# Power.net
KiCad netlist of a schematic drawn in Altium Designer
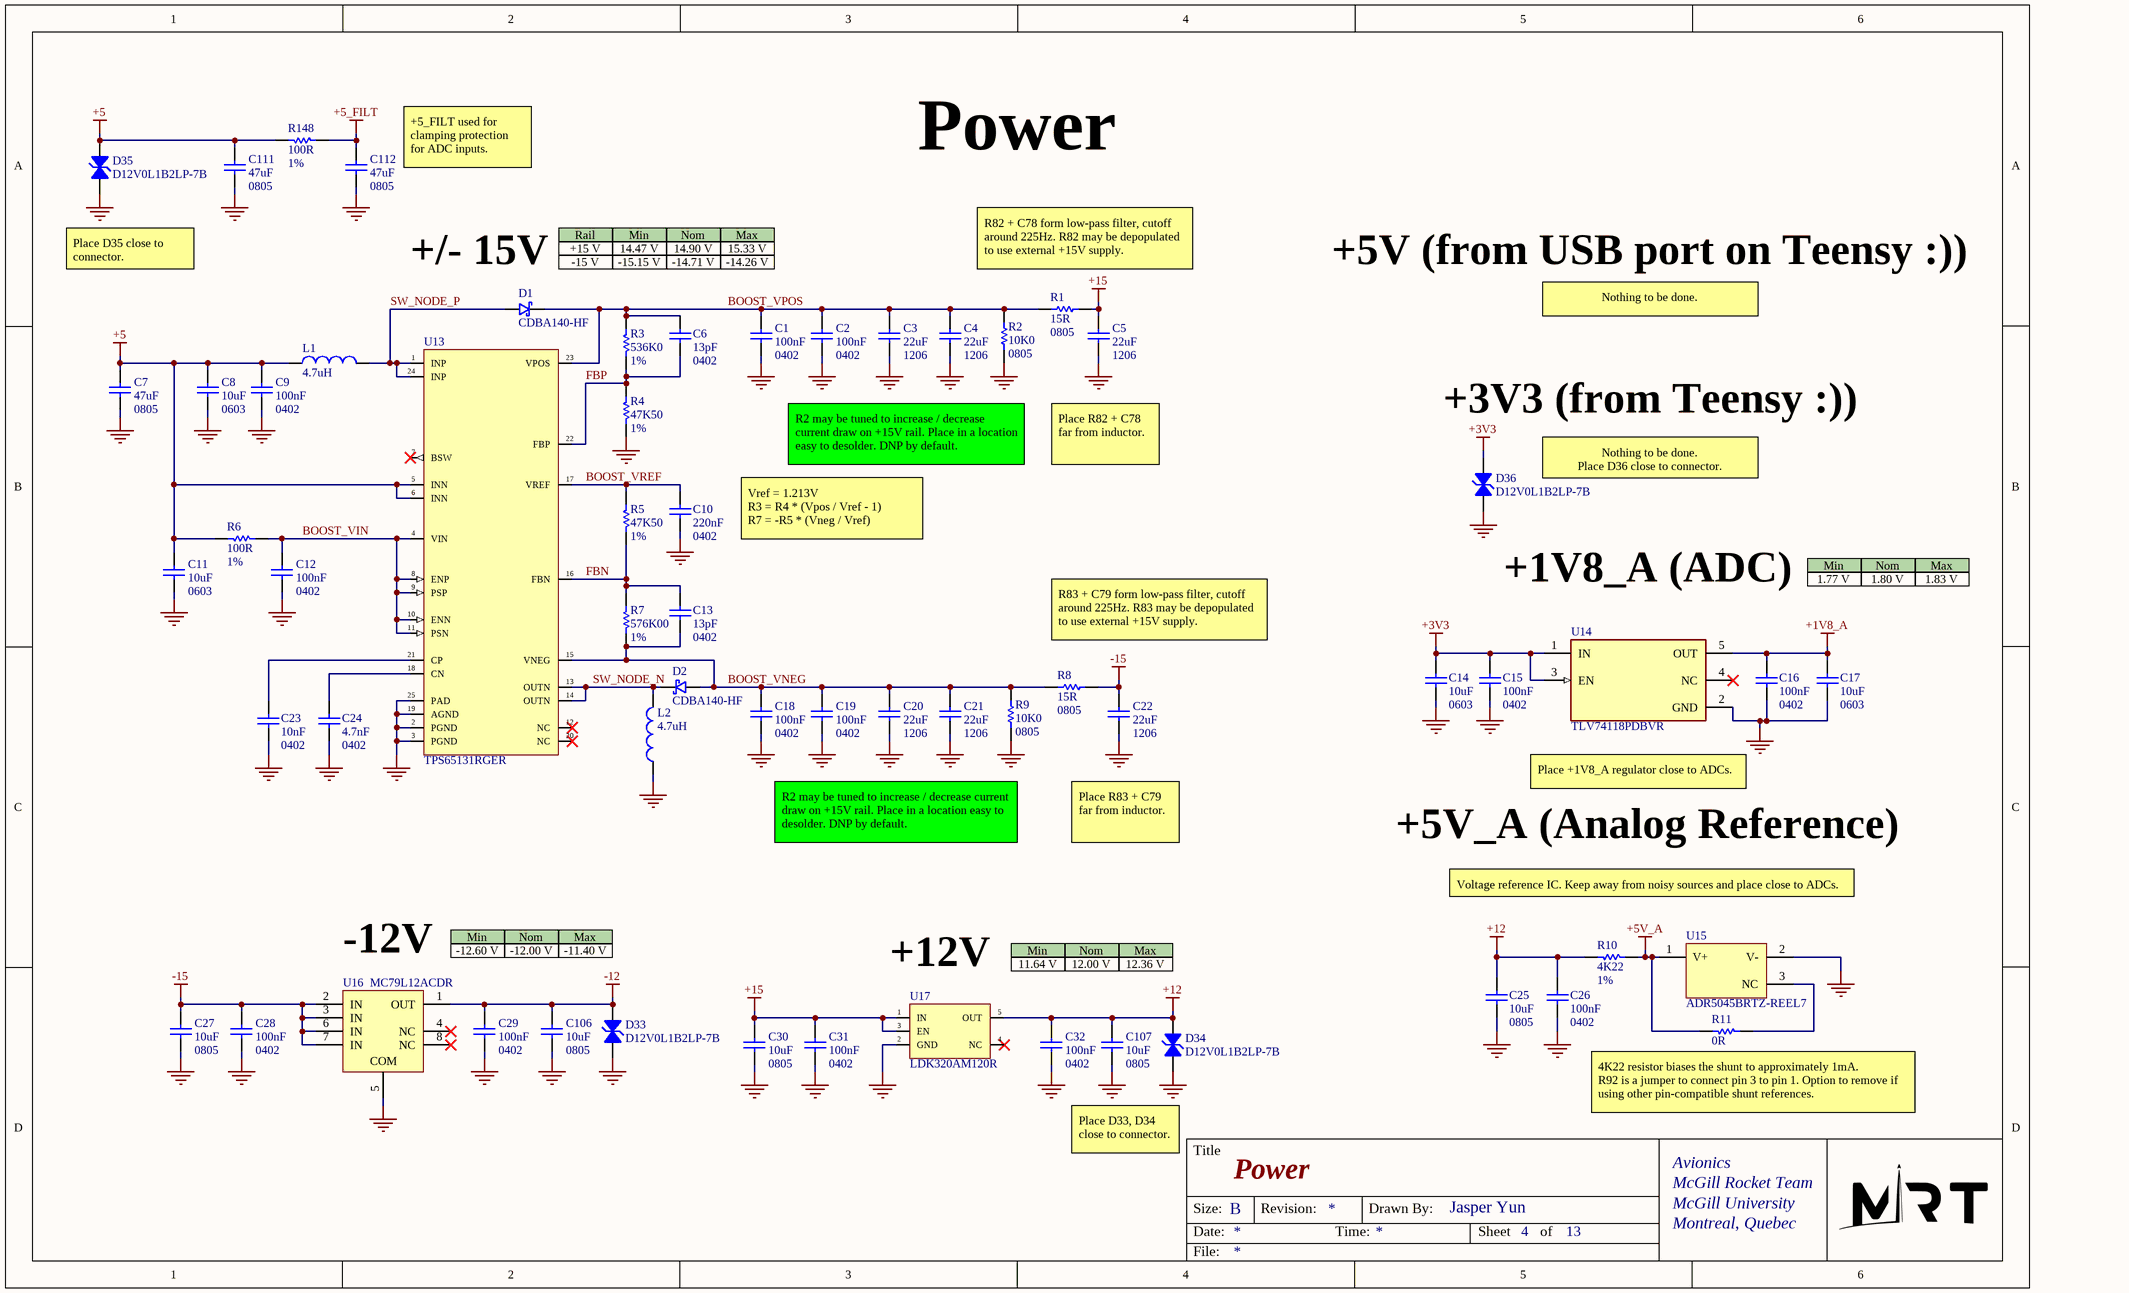
[diagram p0: Power.SchDoc]

(export (version "E")
  (design (tool "Eeschema 10.0.6"))
  (components
    (comp (ref "C1")
      (value "100nF")
      (footprint "0402 CAP")
      (description "Capacitor")
      (fields (field (name "ALTIUM_VALUE") "0402") (field (name "PUBLISHER") "Altium Limited"))
      (libsource (lib "Miscellaneous Devices") (part "Cap"))
    )
    (comp (ref "C2")
      (value "100nF")
      (footprint "0402 CAP")
      (description "Capacitor")
      (fields (field (name "ALTIUM_VALUE") "0402") (field (name "PUBLISHER") "Altium Limited"))
      (libsource (lib "Miscellaneous Devices") (part "Cap"))
    )
    (comp (ref "C3")
      (value "22uF")
      (footprint "1206 CAP")
      (description "Capacitor")
      (fields (field (name "ALTIUM_VALUE") "1206") (field (name "PUBLISHER") "Altium Limited"))
      (libsource (lib "Miscellaneous Devices") (part "Cap"))
    )
    (comp (ref "C4")
      (value "22uF")
      (footprint "1206 CAP")
      (description "Capacitor")
      (fields (field (name "ALTIUM_VALUE") "1206") (field (name "PUBLISHER") "Altium Limited"))
      (libsource (lib "Miscellaneous Devices") (part "Cap"))
    )
    (comp (ref "C5")
      (value "22uF")
      (footprint "1206 CAP")
      (description "Capacitor")
      (fields (field (name "ALTIUM_VALUE") "1206") (field (name "PUBLISHER") "Altium Limited"))
      (libsource (lib "Miscellaneous Devices") (part "Cap"))
    )
    (comp (ref "C6")
      (value "13pF")
      (footprint "0402 CAP")
      (description "Capacitor")
      (fields (field (name "ALTIUM_VALUE") "0402") (field (name "PUBLISHER") "Altium Limited"))
      (libsource (lib "Miscellaneous Devices") (part "Cap"))
    )
    (comp (ref "C7")
      (value "47uF")
      (footprint "0805 CAP")
      (description "Capacitor")
      (fields (field (name "ALTIUM_VALUE") "0805") (field (name "PUBLISHER") "Altium Limited"))
      (libsource (lib "Miscellaneous Devices") (part "Cap"))
    )
    (comp (ref "C8")
      (value "10uF")
      (footprint "0603 CAP SAMSUNG CL10C")
      (description "Capacitor")
      (fields (field (name "ALTIUM_VALUE") "0603") (field (name "PUBLISHER") "Altium Limited"))
      (libsource (lib "Miscellaneous Devices") (part "Cap"))
    )
    (comp (ref "C9")
      (value "100nF")
      (footprint "0402 CAP")
      (description "Capacitor")
      (fields (field (name "ALTIUM_VALUE") "0402") (field (name "PUBLISHER") "Altium Limited"))
      (libsource (lib "Miscellaneous Devices") (part "Cap"))
    )
    (comp (ref "C10")
      (value "220nF")
      (footprint "0402 CAP")
      (description "Capacitor")
      (fields (field (name "ALTIUM_VALUE") "0402") (field (name "PUBLISHER") "Altium Limited"))
      (libsource (lib "Miscellaneous Devices") (part "Cap"))
    )
    (comp (ref "C11")
      (value "10uF")
      (footprint "0603 CAP SAMSUNG CL10C")
      (description "Capacitor")
      (fields (field (name "ALTIUM_VALUE") "0603") (field (name "PUBLISHER") "Altium Limited"))
      (libsource (lib "Miscellaneous Devices") (part "Cap"))
    )
    (comp (ref "C12")
      (value "100nF")
      (footprint "0402 CAP")
      (description "Capacitor")
      (fields (field (name "ALTIUM_VALUE") "0402") (field (name "PUBLISHER") "Altium Limited"))
      (libsource (lib "Miscellaneous Devices") (part "Cap"))
    )
    (comp (ref "C13")
      (value "13pF")
      (footprint "0402 CAP")
      (description "Capacitor")
      (fields (field (name "ALTIUM_VALUE") "0402") (field (name "PUBLISHER") "Altium Limited"))
      (libsource (lib "Miscellaneous Devices") (part "Cap"))
    )
    (comp (ref "C14")
      (value "10uF")
      (footprint "0603 CAP SAMSUNG CL10C")
      (description "Capacitor")
      (fields (field (name "ALTIUM_VALUE") "0603") (field (name "PUBLISHER") "Altium Limited"))
      (libsource (lib "Miscellaneous Devices") (part "Cap"))
    )
    (comp (ref "C15")
      (value "100nF")
      (footprint "0402 CAP")
      (description "Capacitor")
      (fields (field (name "ALTIUM_VALUE") "0402") (field (name "PUBLISHER") "Altium Limited"))
      (libsource (lib "Miscellaneous Devices") (part "Cap"))
    )
    (comp (ref "C16")
      (value "100nF")
      (footprint "0402 CAP")
      (description "Capacitor")
      (fields (field (name "ALTIUM_VALUE") "0402") (field (name "PUBLISHER") "Altium Limited"))
      (libsource (lib "Miscellaneous Devices") (part "Cap"))
    )
    (comp (ref "C17")
      (value "10uF")
      (footprint "0603 CAP SAMSUNG CL10C")
      (description "Capacitor")
      (fields (field (name "ALTIUM_VALUE") "0603") (field (name "PUBLISHER") "Altium Limited"))
      (libsource (lib "Miscellaneous Devices") (part "Cap"))
    )
    (comp (ref "C18")
      (value "100nF")
      (footprint "0402 CAP")
      (description "Capacitor")
      (fields (field (name "ALTIUM_VALUE") "0402") (field (name "PUBLISHER") "Altium Limited"))
      (libsource (lib "Miscellaneous Devices") (part "Cap"))
    )
    (comp (ref "C19")
      (value "100nF")
      (footprint "0402 CAP")
      (description "Capacitor")
      (fields (field (name "ALTIUM_VALUE") "0402") (field (name "PUBLISHER") "Altium Limited"))
      (libsource (lib "Miscellaneous Devices") (part "Cap"))
    )
    (comp (ref "C20")
      (value "22uF")
      (footprint "1206 CAP")
      (description "Capacitor")
      (fields (field (name "ALTIUM_VALUE") "1206") (field (name "PUBLISHER") "Altium Limited"))
      (libsource (lib "Miscellaneous Devices") (part "Cap"))
    )
    (comp (ref "C21")
      (value "22uF")
      (footprint "1206 CAP")
      (description "Capacitor")
      (fields (field (name "ALTIUM_VALUE") "1206") (field (name "PUBLISHER") "Altium Limited"))
      (libsource (lib "Miscellaneous Devices") (part "Cap"))
    )
    (comp (ref "C22")
      (value "22uF")
      (footprint "1206 CAP")
      (description "Capacitor")
      (fields (field (name "ALTIUM_VALUE") "1206") (field (name "PUBLISHER") "Altium Limited"))
      (libsource (lib "Miscellaneous Devices") (part "Cap"))
    )
    (comp (ref "C23")
      (value "10nF")
      (footprint "0402 CAP")
      (description "Capacitor")
      (fields (field (name "ALTIUM_VALUE") "0402") (field (name "PUBLISHER") "Altium Limited"))
      (libsource (lib "Miscellaneous Devices") (part "Cap"))
    )
    (comp (ref "C24")
      (value "4.7nF")
      (footprint "0402 CAP")
      (description "Capacitor")
      (fields (field (name "ALTIUM_VALUE") "0402") (field (name "PUBLISHER") "Altium Limited"))
      (libsource (lib "Miscellaneous Devices") (part "Cap"))
    )
    (comp (ref "C25")
      (value "10uF")
      (footprint "0805 CAP")
      (description "Capacitor")
      (fields (field (name "ALTIUM_VALUE") "0805") (field (name "PUBLISHER") "Altium Limited"))
      (libsource (lib "Miscellaneous Devices") (part "Cap"))
    )
    (comp (ref "C26")
      (value "100nF")
      (footprint "0402 CAP")
      (description "Capacitor")
      (fields (field (name "ALTIUM_VALUE") "0402") (field (name "PUBLISHER") "Altium Limited"))
      (libsource (lib "Miscellaneous Devices") (part "Cap"))
    )
    (comp (ref "C27")
      (value "10uF")
      (footprint "0805 CAP")
      (description "Capacitor")
      (fields (field (name "ALTIUM_VALUE") "0805") (field (name "PUBLISHER") "Altium Limited"))
      (libsource (lib "Miscellaneous Devices") (part "Cap"))
    )
    (comp (ref "C28")
      (value "100nF")
      (footprint "0402 CAP")
      (description "Capacitor")
      (fields (field (name "ALTIUM_VALUE") "0402") (field (name "PUBLISHER") "Altium Limited"))
      (libsource (lib "Miscellaneous Devices") (part "Cap"))
    )
    (comp (ref "C29")
      (value "100nF")
      (footprint "0402 CAP")
      (description "Capacitor")
      (fields (field (name "ALTIUM_VALUE") "0402") (field (name "PUBLISHER") "Altium Limited"))
      (libsource (lib "Miscellaneous Devices") (part "Cap"))
    )
    (comp (ref "C30")
      (value "10uF")
      (footprint "0805 CAP")
      (description "Capacitor")
      (fields (field (name "ALTIUM_VALUE") "0805") (field (name "PUBLISHER") "Altium Limited"))
      (libsource (lib "Miscellaneous Devices") (part "Cap"))
    )
    (comp (ref "C31")
      (value "100nF")
      (footprint "0402 CAP")
      (description "Capacitor")
      (fields (field (name "ALTIUM_VALUE") "0402") (field (name "PUBLISHER") "Altium Limited"))
      (libsource (lib "Miscellaneous Devices") (part "Cap"))
    )
    (comp (ref "C32")
      (value "100nF")
      (footprint "0402 CAP")
      (description "Capacitor")
      (fields (field (name "ALTIUM_VALUE") "0402") (field (name "PUBLISHER") "Altium Limited"))
      (libsource (lib "Miscellaneous Devices") (part "Cap"))
    )
    (comp (ref "C106")
      (value "10uF")
      (footprint "0805 CAP")
      (description "Capacitor")
      (fields (field (name "ALTIUM_VALUE") "0805") (field (name "PUBLISHER") "Altium Limited"))
      (libsource (lib "Miscellaneous Devices") (part "Cap"))
    )
    (comp (ref "C107")
      (value "10uF")
      (footprint "0805 CAP")
      (description "Capacitor")
      (fields (field (name "ALTIUM_VALUE") "0805") (field (name "PUBLISHER") "Altium Limited"))
      (libsource (lib "Miscellaneous Devices") (part "Cap"))
    )
    (comp (ref "C111")
      (value "47uF")
      (footprint "0805 CAP")
      (description "Capacitor")
      (fields (field (name "ALTIUM_VALUE") "0805") (field (name "PUBLISHER") "Altium Limited"))
      (libsource (lib "Miscellaneous Devices") (part "Cap"))
    )
    (comp (ref "C112")
      (value "47uF")
      (footprint "0805 CAP")
      (description "Capacitor")
      (fields (field (name "ALTIUM_VALUE") "0805") (field (name "PUBLISHER") "Altium Limited"))
      (libsource (lib "Miscellaneous Devices") (part "Cap"))
    )
    (comp (ref "D1")
      (value "CDBA140-HF")
      (footprint "Diode SMA")
      (description "Generic Schottky Diode")
      (libsource (lib "MRT SCH Library") (part "Schottky Diode"))
    )
    (comp (ref "D2")
      (value "CDBA140-HF")
      (footprint "Diode SMA")
      (description "Generic Schottky Diode")
      (libsource (lib "MRT SCH Library") (part "Schottky Diode"))
    )
    (comp (ref "D33")
      (value "D12V0L1B2LP-7B")
      (footprint "DFN1006-2")
      (description "Bidirectional Zener diode")
      (libsource (lib "MRT SCH Library") (part "Diode Zener Bidirectional"))
    )
    (comp (ref "D34")
      (value "D12V0L1B2LP-7B")
      (footprint "DFN1006-2")
      (description "Bidirectional Zener diode")
      (libsource (lib "MRT SCH Library") (part "Diode Zener Bidirectional"))
    )
    (comp (ref "D35")
      (value "D12V0L1B2LP-7B")
      (footprint "DFN1006-2")
      (description "Bidirectional Zener diode")
      (libsource (lib "MRT SCH Library") (part "Diode Zener Bidirectional"))
    )
    (comp (ref "D36")
      (value "D12V0L1B2LP-7B")
      (footprint "DFN1006-2")
      (description "Bidirectional Zener diode")
      (libsource (lib "MRT SCH Library") (part "Diode Zener Bidirectional"))
    )
    (comp (ref "L1")
      (value "4.7uH")
      (footprint "Inductor BWVS005050403R3M00")
      (description "4.7uH  BWVS005050404R7M00")
      (fields (field (name "PUBLISHER") "Altium Limited"))
      (libsource (lib "Miscellaneous Devices") (part "Inductor"))
    )
    (comp (ref "L2")
      (value "4.7uH")
      (footprint "Inductor BWVS005050403R3M00")
      (description "4.7uH  BWVS005050404R7M00")
      (fields (field (name "PUBLISHER") "Altium Limited"))
      (libsource (lib "Miscellaneous Devices") (part "Inductor"))
    )
    (comp (ref "R1")
      (value "15R")
      (footprint "0805 RES")
      (description "Resistor")
      (fields (field (name "ALTIUM_VALUE") "0805") (field (name "PUBLISHER") "Altium Limited"))
      (libsource (lib "Miscellaneous Devices") (part "Res1"))
    )
    (comp (ref "R2")
      (value "10K0")
      (footprint "0805 RES")
      (description "Resistor")
      (fields (field (name "ALTIUM_VALUE") "0805") (field (name "PUBLISHER") "Altium Limited"))
      (libsource (lib "Miscellaneous Devices") (part "Res1"))
    )
    (comp (ref "R3")
      (value "536K0")
      (footprint "0402 RES")
      (description "Resistor")
      (fields (field (name "ALTIUM_VALUE") "1%") (field (name "PUBLISHER") "Altium Limited"))
      (libsource (lib "Miscellaneous Devices") (part "Res1"))
    )
    (comp (ref "R4")
      (value "47K50")
      (footprint "0402 RES")
      (description "Resistor")
      (fields (field (name "ALTIUM_VALUE") "1%") (field (name "PUBLISHER") "Altium Limited"))
      (libsource (lib "Miscellaneous Devices") (part "Res1"))
    )
    (comp (ref "R5")
      (value "47K50")
      (footprint "0402 RES")
      (description "Resistor")
      (fields (field (name "ALTIUM_VALUE") "1%") (field (name "PUBLISHER") "Altium Limited"))
      (libsource (lib "Miscellaneous Devices") (part "Res1"))
    )
    (comp (ref "R6")
      (value "100R")
      (footprint "0402 RES")
      (description "Resistor")
      (fields (field (name "ALTIUM_VALUE") "1%") (field (name "PUBLISHER") "Altium Limited"))
      (libsource (lib "Miscellaneous Devices") (part "Res1"))
    )
    (comp (ref "R7")
      (value "576K00")
      (footprint "0402 RES")
      (description "Resistor")
      (fields (field (name "ALTIUM_VALUE") "1%") (field (name "PUBLISHER") "Altium Limited"))
      (libsource (lib "Miscellaneous Devices") (part "Res1"))
    )
    (comp (ref "R8")
      (value "15R")
      (footprint "0805 RES")
      (description "Resistor")
      (fields (field (name "ALTIUM_VALUE") "0805") (field (name "PUBLISHER") "Altium Limited"))
      (libsource (lib "Miscellaneous Devices") (part "Res1"))
    )
    (comp (ref "R9")
      (value "10K0")
      (footprint "0805 RES")
      (description "Resistor")
      (fields (field (name "ALTIUM_VALUE") "0805") (field (name "PUBLISHER") "Altium Limited"))
      (libsource (lib "Miscellaneous Devices") (part "Res1"))
    )
    (comp (ref "R10")
      (value "4K22")
      (footprint "0402 RES")
      (description "Resistor")
      (fields (field (name "ALTIUM_VALUE") "1%") (field (name "PUBLISHER") "Altium Limited"))
      (libsource (lib "Miscellaneous Devices") (part "Res1"))
    )
    (comp (ref "R11")
      (value "0R")
      (footprint "0402 RES")
      (description "Resistor")
      (fields (field (name "PUBLISHER") "Altium Limited"))
      (libsource (lib "Miscellaneous Devices") (part "Res1"))
    )
    (comp (ref "R148")
      (value "100R")
      (footprint "0402 RES")
      (description "Resistor")
      (fields (field (name "ALTIUM_VALUE") "1%") (field (name "PUBLISHER") "Altium Limited"))
      (libsource (lib "Miscellaneous Devices") (part "Res1"))
    )
    (comp (ref "U13")
      (value "TPS65131RGER")
      (footprint "VQFN-24")
      (description "IC REG BUCK BST INV ADJ DL 24QFN")
      (fields (field (name "MANUFACTURER") "Texas Instruments"))
      (libsource (lib "MRT SCH Library") (part "Dual Boost TPS65131RGER"))
    )
    (comp (ref "U14")
      (value "TLV74118PDBVR")
      (footprint "FP-DBV0005A-IPC_A")
      (description "None")
      (libsource (lib "Altium Content Vault") (part "843f007849b3ee74adb27ff62509038"))
    )
    (comp (ref "U15")
      (value "ADR5045BRTZ-REEL7")
      (footprint "ADI-RT-3_M")
      (fields (field (name "MANUFACTURER") "Analog Devices"))
      (libsource (lib "Altium Content Vault") (part "ADI-ADR158x_504x-RT_KS-3"))
    )
    (comp (ref "U16")
      (value "MC79L12ACDR")
      (footprint "D0008A_M")
      (fields (field (name "MANUFACTURER") "Texas Instruments"))
      (libsource (lib "Altium Content Vault") (part "TI-MC79L12AD8"))
    )
    (comp (ref "U17")
      (value "LDK320AM120R")
      (footprint "SOT23-5")
      (description "200 mA low quiescent current and high PSRR voltage regulator")
      (fields (field (name "MANUFACTURER") "STMicroelectronics"))
      (libsource (lib "MRT SCH Library") (part "VREG Linear LDK320AM120R"))
    )
  )
  (nets
    (net (code "1") (name "+1V8_A") (class "Default")
      (node (ref "C16") (pin "2") (pinfunction "2_2") (pintype "passive"))
      (node (ref "C17") (pin "2") (pinfunction "2_2") (pintype "passive"))
      (node (ref "U14") (pin "5") (pinfunction "OUT_5") (pintype "power_in"))
    )
    (net (code "2") (name "+3V3") (class "Default")
      (node (ref "C14") (pin "2") (pinfunction "2_2") (pintype "passive"))
      (node (ref "C15") (pin "2") (pinfunction "2_2") (pintype "passive"))
      (node (ref "D36") (pin "2") (pinfunction "2_2") (pintype "passive"))
      (node (ref "U14") (pin "1") (pinfunction "IN_1") (pintype "power_in"))
      (node (ref "U14") (pin "3") (pinfunction "EN_3") (pintype "input"))
    )
    (net (code "3") (name "+5") (class "Default")
      (node (ref "C11") (pin "2") (pinfunction "2_2") (pintype "passive"))
      (node (ref "C111") (pin "2") (pinfunction "2_2") (pintype "passive"))
      (node (ref "C7") (pin "2") (pinfunction "2_2") (pintype "passive"))
      (node (ref "C8") (pin "2") (pinfunction "2_2") (pintype "passive"))
      (node (ref "C9") (pin "2") (pinfunction "2_2") (pintype "passive"))
      (node (ref "D35") (pin "2") (pinfunction "2_2") (pintype "passive"))
      (node (ref "L1") (pin "1") (pinfunction "1_1") (pintype "passive"))
      (node (ref "R148") (pin "1") (pinfunction "1_1") (pintype "passive"))
      (node (ref "R6") (pin "1") (pinfunction "1_1") (pintype "passive"))
      (node (ref "U13") (pin "5") (pinfunction "INN_5") (pintype "passive"))
      (node (ref "U13") (pin "6") (pinfunction "INN_6") (pintype "passive"))
    )
    (net (code "4") (name "+5V_A") (class "Default")
      (node (ref "R10") (pin "2") (pinfunction "2_2") (pintype "passive"))
      (node (ref "R11") (pin "1") (pinfunction "1_1") (pintype "passive"))
      (node (ref "U15") (pin "1") (pinfunction "V+_1") (pintype "power_in"))
    )
    (net (code "5") (name "+5_FILT") (class "Default")
      (node (ref "C112") (pin "2") (pinfunction "2_2") (pintype "passive"))
      (node (ref "R148") (pin "2") (pinfunction "2_2") (pintype "passive"))
    )
    (net (code "6") (name "+12") (class "Default")
      (node (ref "C107") (pin "2") (pinfunction "2_2") (pintype "passive"))
      (node (ref "C25") (pin "2") (pinfunction "2_2") (pintype "passive"))
      (node (ref "C26") (pin "2") (pinfunction "2_2") (pintype "passive"))
      (node (ref "C32") (pin "2") (pinfunction "2_2") (pintype "passive"))
      (node (ref "D34") (pin "2") (pinfunction "2_2") (pintype "passive"))
      (node (ref "R10") (pin "1") (pinfunction "1_1") (pintype "passive"))
      (node (ref "U17") (pin "5") (pinfunction "OUT_5") (pintype "passive"))
    )
    (net (code "7") (name "+15") (class "Default")
      (node (ref "C30") (pin "2") (pinfunction "2_2") (pintype "passive"))
      (node (ref "C31") (pin "2") (pinfunction "2_2") (pintype "passive"))
      (node (ref "C5") (pin "2") (pinfunction "2_2") (pintype "passive"))
      (node (ref "R1") (pin "1") (pinfunction "1_1") (pintype "passive"))
      (node (ref "U17") (pin "1") (pinfunction "IN_1") (pintype "passive"))
      (node (ref "U17") (pin "3") (pinfunction "EN_3") (pintype "passive"))
    )
    (net (code "8") (name "-12") (class "Default")
      (node (ref "C106") (pin "2") (pinfunction "2_2") (pintype "passive"))
      (node (ref "C29") (pin "2") (pinfunction "2_2") (pintype "passive"))
      (node (ref "D33") (pin "2") (pinfunction "2_2") (pintype "passive"))
      (node (ref "U16") (pin "1") (pinfunction "OUT_1") (pintype "power_in"))
    )
    (net (code "9") (name "-15") (class "Default")
      (node (ref "C22") (pin "2") (pinfunction "2_2") (pintype "passive"))
      (node (ref "C27") (pin "2") (pinfunction "2_2") (pintype "passive"))
      (node (ref "C28") (pin "2") (pinfunction "2_2") (pintype "passive"))
      (node (ref "R8") (pin "1") (pinfunction "1_1") (pintype "passive"))
      (node (ref "U16") (pin "2") (pinfunction "IN_2") (pintype "power_in"))
      (node (ref "U16") (pin "3") (pinfunction "IN_3") (pintype "power_in"))
      (node (ref "U16") (pin "6") (pinfunction "IN_6") (pintype "power_in"))
      (node (ref "U16") (pin "7") (pinfunction "IN_7") (pintype "power_in"))
    )
    (net (code "10") (name "/BOOST_VIN") (class "Default")
      (node (ref "C12") (pin "2") (pinfunction "2_2") (pintype "passive"))
      (node (ref "R6") (pin "2") (pinfunction "2_2") (pintype "passive"))
      (node (ref "U13") (pin "10") (pinfunction "ENN_10") (pintype "input"))
      (node (ref "U13") (pin "11") (pinfunction "PSN_11") (pintype "input"))
      (node (ref "U13") (pin "4") (pinfunction "VIN_4") (pintype "passive"))
      (node (ref "U13") (pin "8") (pinfunction "ENP_8") (pintype "input"))
      (node (ref "U13") (pin "9") (pinfunction "PSP_9") (pintype "input"))
    )
    (net (code "11") (name "/BOOST_VNEG") (class "Default")
      (node (ref "C13") (pin "1") (pinfunction "1_1") (pintype "passive"))
      (node (ref "C18") (pin "2") (pinfunction "2_2") (pintype "passive"))
      (node (ref "C19") (pin "2") (pinfunction "2_2") (pintype "passive"))
      (node (ref "C20") (pin "2") (pinfunction "2_2") (pintype "passive"))
      (node (ref "C21") (pin "2") (pinfunction "2_2") (pintype "passive"))
      (node (ref "D2") (pin "2") (pinfunction "Anode_2") (pintype "passive"))
      (node (ref "R7") (pin "1") (pinfunction "1_1") (pintype "passive"))
      (node (ref "R8") (pin "2") (pinfunction "2_2") (pintype "passive"))
      (node (ref "R9") (pin "2") (pinfunction "2_2") (pintype "passive"))
      (node (ref "U13") (pin "15") (pinfunction "VNEG_15") (pintype "passive"))
    )
    (net (code "12") (name "/BOOST_VPOS") (class "Default")
      (node (ref "C1") (pin "2") (pinfunction "2_2") (pintype "passive"))
      (node (ref "C2") (pin "2") (pinfunction "2_2") (pintype "passive"))
      (node (ref "C3") (pin "2") (pinfunction "2_2") (pintype "passive"))
      (node (ref "C4") (pin "2") (pinfunction "2_2") (pintype "passive"))
      (node (ref "C6") (pin "1") (pinfunction "1_1") (pintype "passive"))
      (node (ref "D1") (pin "1") (pinfunction "Cathode_1") (pintype "passive"))
      (node (ref "R1") (pin "2") (pinfunction "2_2") (pintype "passive"))
      (node (ref "R2") (pin "2") (pinfunction "2_2") (pintype "passive"))
      (node (ref "R3") (pin "1") (pinfunction "1_1") (pintype "passive"))
      (node (ref "U13") (pin "23") (pinfunction "VPOS_23") (pintype "passive"))
    )
    (net (code "13") (name "/BOOST_VREF") (class "Default")
      (node (ref "C10") (pin "1") (pinfunction "1_1") (pintype "passive"))
      (node (ref "R5") (pin "1") (pinfunction "1_1") (pintype "passive"))
      (node (ref "U13") (pin "17") (pinfunction "VREF_17") (pintype "passive"))
    )
    (net (code "14") (name "/FBN") (class "Default")
      (node (ref "C13") (pin "2") (pinfunction "2_2") (pintype "passive"))
      (node (ref "R5") (pin "2") (pinfunction "2_2") (pintype "passive"))
      (node (ref "R7") (pin "2") (pinfunction "2_2") (pintype "passive"))
      (node (ref "U13") (pin "16") (pinfunction "FBN_16") (pintype "passive"))
    )
    (net (code "15") (name "/FBP") (class "Default")
      (node (ref "C6") (pin "2") (pinfunction "2_2") (pintype "passive"))
      (node (ref "R3") (pin "2") (pinfunction "2_2") (pintype "passive"))
      (node (ref "R4") (pin "1") (pinfunction "1_1") (pintype "passive"))
      (node (ref "U13") (pin "22") (pinfunction "FBP_22") (pintype "passive"))
    )
    (net (code "16") (name "/SW_NODE_N") (class "Default")
      (node (ref "D2") (pin "1") (pinfunction "Cathode_1") (pintype "passive"))
      (node (ref "L2") (pin "2") (pinfunction "2_2") (pintype "passive"))
      (node (ref "U13") (pin "13") (pinfunction "OUTN_13") (pintype "passive"))
      (node (ref "U13") (pin "14") (pinfunction "OUTN_14") (pintype "passive"))
    )
    (net (code "17") (name "/SW_NODE_P") (class "Default")
      (node (ref "D1") (pin "2") (pinfunction "Anode_2") (pintype "passive"))
      (node (ref "L1") (pin "2") (pinfunction "2_2") (pintype "passive"))
      (node (ref "U13") (pin "1") (pinfunction "INP_1") (pintype "passive"))
      (node (ref "U13") (pin "24") (pinfunction "INP_24") (pintype "passive"))
    )
    (net (code "18") (name "GND") (class "Default")
      (node (ref "C1") (pin "1") (pinfunction "1_1") (pintype "passive"))
      (node (ref "C10") (pin "2") (pinfunction "2_2") (pintype "passive"))
      (node (ref "C106") (pin "1") (pinfunction "1_1") (pintype "passive"))
      (node (ref "C107") (pin "1") (pinfunction "1_1") (pintype "passive"))
      (node (ref "C11") (pin "1") (pinfunction "1_1") (pintype "passive"))
      (node (ref "C111") (pin "1") (pinfunction "1_1") (pintype "passive"))
      (node (ref "C112") (pin "1") (pinfunction "1_1") (pintype "passive"))
      (node (ref "C12") (pin "1") (pinfunction "1_1") (pintype "passive"))
      (node (ref "C14") (pin "1") (pinfunction "1_1") (pintype "passive"))
      (node (ref "C15") (pin "1") (pinfunction "1_1") (pintype "passive"))
      (node (ref "C16") (pin "1") (pinfunction "1_1") (pintype "passive"))
      (node (ref "C17") (pin "1") (pinfunction "1_1") (pintype "passive"))
      (node (ref "C18") (pin "1") (pinfunction "1_1") (pintype "passive"))
      (node (ref "C19") (pin "1") (pinfunction "1_1") (pintype "passive"))
      (node (ref "C2") (pin "1") (pinfunction "1_1") (pintype "passive"))
      (node (ref "C20") (pin "1") (pinfunction "1_1") (pintype "passive"))
      (node (ref "C21") (pin "1") (pinfunction "1_1") (pintype "passive"))
      (node (ref "C22") (pin "1") (pinfunction "1_1") (pintype "passive"))
      (node (ref "C23") (pin "1") (pinfunction "1_1") (pintype "passive"))
      (node (ref "C24") (pin "1") (pinfunction "1_1") (pintype "passive"))
      (node (ref "C25") (pin "1") (pinfunction "1_1") (pintype "passive"))
      (node (ref "C26") (pin "1") (pinfunction "1_1") (pintype "passive"))
      (node (ref "C27") (pin "1") (pinfunction "1_1") (pintype "passive"))
      (node (ref "C28") (pin "1") (pinfunction "1_1") (pintype "passive"))
      (node (ref "C29") (pin "1") (pinfunction "1_1") (pintype "passive"))
      (node (ref "C3") (pin "1") (pinfunction "1_1") (pintype "passive"))
      (node (ref "C30") (pin "1") (pinfunction "1_1") (pintype "passive"))
      (node (ref "C31") (pin "1") (pinfunction "1_1") (pintype "passive"))
      (node (ref "C32") (pin "1") (pinfunction "1_1") (pintype "passive"))
      (node (ref "C4") (pin "1") (pinfunction "1_1") (pintype "passive"))
      (node (ref "C5") (pin "1") (pinfunction "1_1") (pintype "passive"))
      (node (ref "C7") (pin "1") (pinfunction "1_1") (pintype "passive"))
      (node (ref "C8") (pin "1") (pinfunction "1_1") (pintype "passive"))
      (node (ref "C9") (pin "1") (pinfunction "1_1") (pintype "passive"))
      (node (ref "D33") (pin "1") (pinfunction "1_1") (pintype "passive"))
      (node (ref "D34") (pin "1") (pinfunction "1_1") (pintype "passive"))
      (node (ref "D35") (pin "1") (pinfunction "1_1") (pintype "passive"))
      (node (ref "D36") (pin "1") (pinfunction "1_1") (pintype "passive"))
      (node (ref "L2") (pin "1") (pinfunction "1_1") (pintype "passive"))
      (node (ref "R2") (pin "1") (pinfunction "1_1") (pintype "passive"))
      (node (ref "R4") (pin "2") (pinfunction "2_2") (pintype "passive"))
      (node (ref "R9") (pin "1") (pinfunction "1_1") (pintype "passive"))
      (node (ref "U13") (pin "19") (pinfunction "AGND_19") (pintype "passive"))
      (node (ref "U13") (pin "2") (pinfunction "PGND_2") (pintype "passive"))
      (node (ref "U13") (pin "25") (pinfunction "PAD_25") (pintype "passive"))
      (node (ref "U13") (pin "3") (pinfunction "PGND_3") (pintype "passive"))
      (node (ref "U14") (pin "2") (pinfunction "GND_2") (pintype "power_in"))
      (node (ref "U15") (pin "2") (pinfunction "V-_2") (pintype "power_in"))
      (node (ref "U16") (pin "5") (pinfunction "COM_5") (pintype "power_in"))
      (node (ref "U17") (pin "2") (pinfunction "GND_2") (pintype "passive"))
    )
    (net (code "19") (name "Net-(U13-CN)") (class "Default")
      (node (ref "C24") (pin "2") (pinfunction "2_2") (pintype "passive"))
      (node (ref "U13") (pin "18") (pinfunction "CN_18") (pintype "passive"))
    )
    (net (code "20") (name "Net-(U13-CP)") (class "Default")
      (node (ref "C23") (pin "2") (pinfunction "2_2") (pintype "passive"))
      (node (ref "U13") (pin "21") (pinfunction "CP_21") (pintype "passive"))
    )
    (net (code "21") (name "Net-(U15-NC)") (class "Default")
      (node (ref "R11") (pin "2") (pinfunction "2_2") (pintype "passive"))
      (node (ref "U15") (pin "3") (pinfunction "NC_3") (pintype "passive"))
    )
    (net (code "22") (name "unconnected-(U13-BSW-Pad7)") (class "Default")
      (node (ref "U13") (pin "7") (pinfunction "BSW_7") (pintype "output+no_connect"))
    )
    (net (code "23") (name "unconnected-(U13-NC-Pad12)") (class "Default")
      (node (ref "U13") (pin "12") (pinfunction "NC_12") (pintype "passive+no_connect"))
    )
    (net (code "24") (name "unconnected-(U13-NC-Pad20)") (class "Default")
      (node (ref "U13") (pin "20") (pinfunction "NC_20") (pintype "passive+no_connect"))
    )
    (net (code "25") (name "unconnected-(U14-NC-Pad4)") (class "Default")
      (node (ref "U14") (pin "4") (pinfunction "NC_4") (pintype "passive+no_connect"))
    )
    (net (code "26") (name "unconnected-(U16-NC-Pad4)") (class "Default")
      (node (ref "U16") (pin "4") (pinfunction "NC_4") (pintype "passive+no_connect"))
    )
    (net (code "27") (name "unconnected-(U16-NC-Pad8)") (class "Default")
      (node (ref "U16") (pin "8") (pinfunction "NC_8") (pintype "passive+no_connect"))
    )
    (net (code "28") (name "unconnected-(U17-NC-Pad4)") (class "Default")
      (node (ref "U17") (pin "4") (pinfunction "NC_4") (pintype "passive+no_connect"))
    )
  )
)
